# BRZ_BATT_MGR.net
KiCad netlist of a schematic drawn in Altium Designer
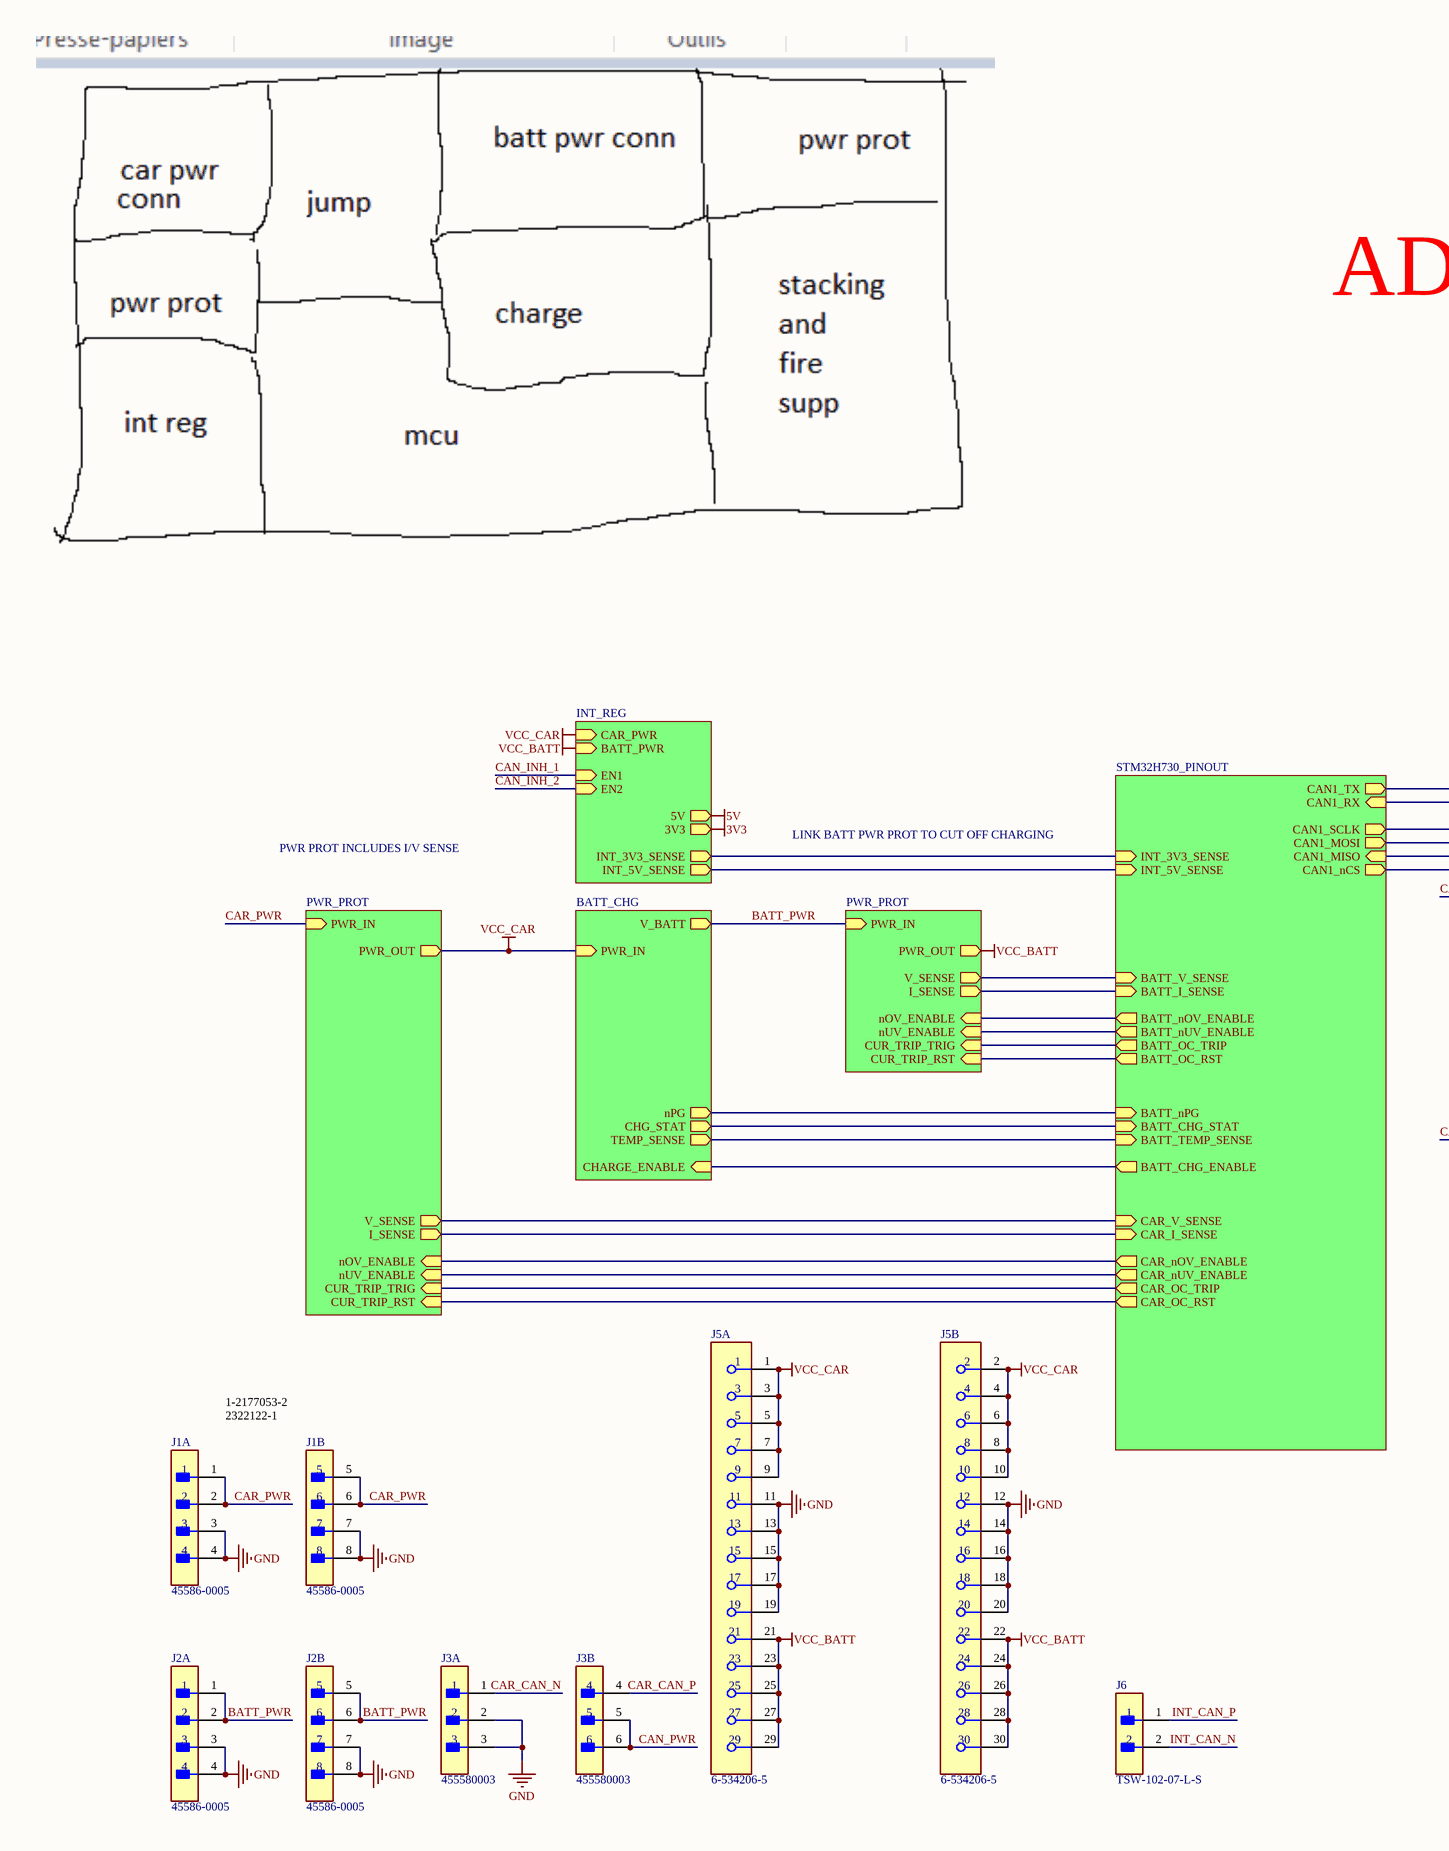
[diagram p0: BRZ_BATT_MGR.SchDoc, left]
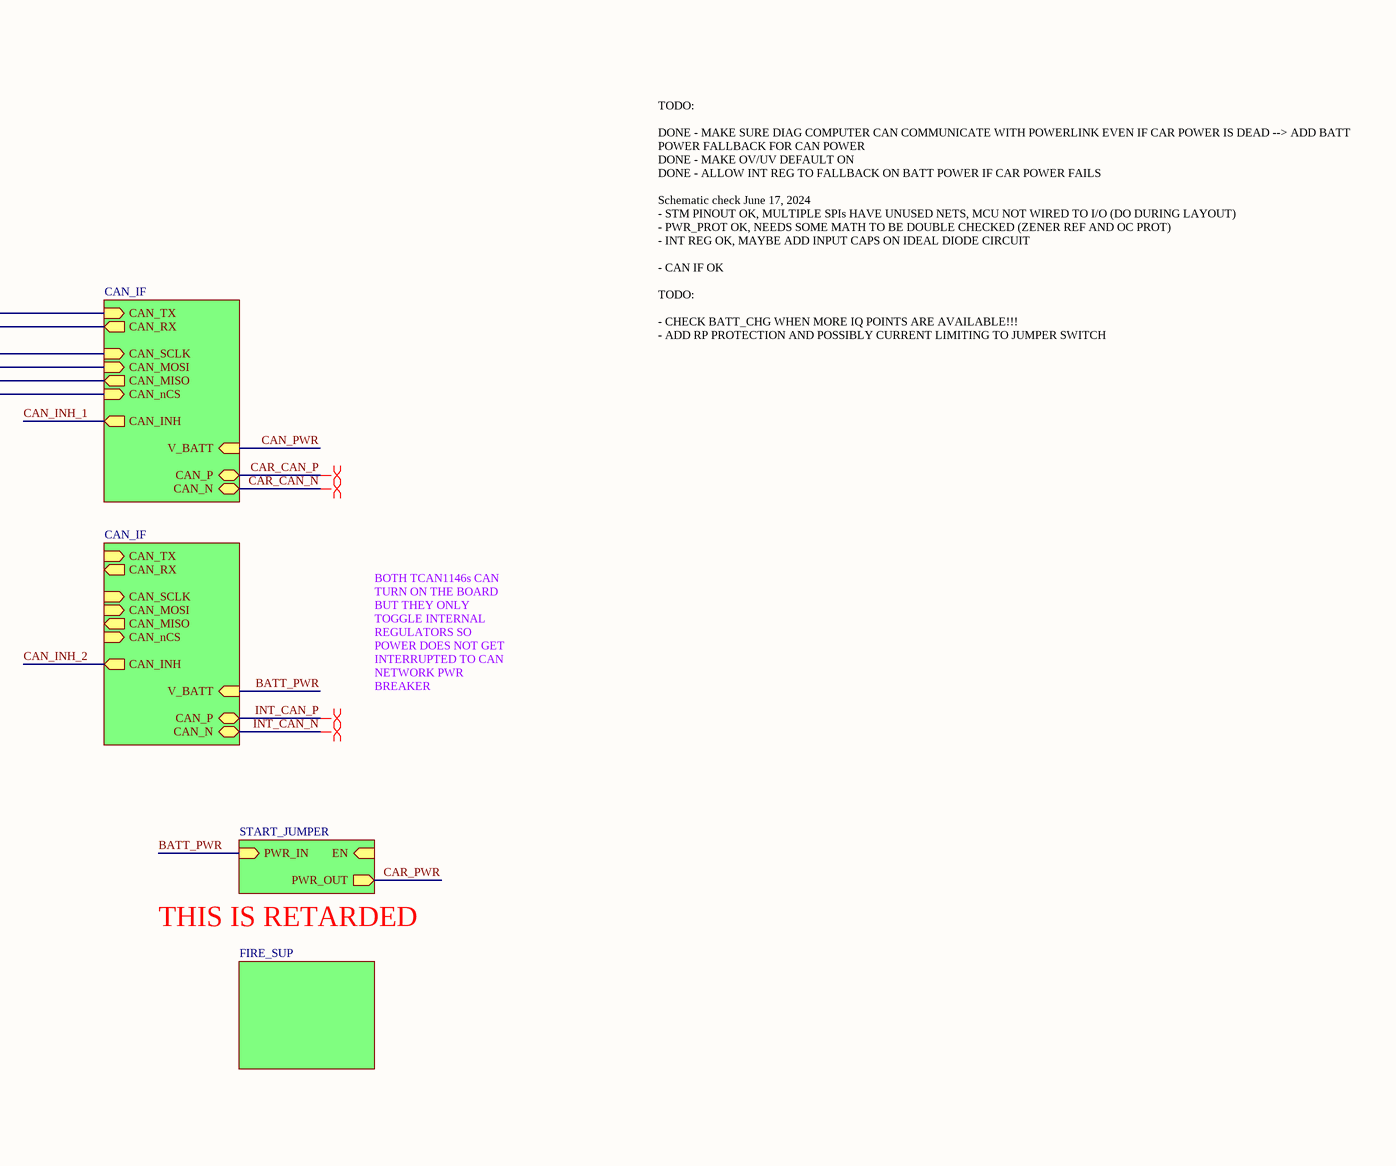
[diagram p1: BRZ_BATT_MGR.SchDoc, right]

(export (version "E")
  (design (tool "Eeschema 10.0.6"))
  (components
    (comp (ref "J1")
      (value "45586-0005")
      (footprint "FP-45586-0005-MFG")
      (description "CONN HEADER R/A 8POS 4.2MM")
      (libsource (lib "Altium Content Vault") (part "85438c39ca9ef07d43bb2e97c52bc44"))
    )
    (comp (ref "J2")
      (value "45586-0005")
      (footprint "FP-45586-0005-MFG")
      (description "CONN HEADER R/A 8POS 4.2MM")
      (libsource (lib "Altium Content Vault") (part "85438c39ca9ef07d43bb2e97c52bc44"))
    )
    (comp (ref "J3")
      (value "455580003")
      (footprint "FP-455580003-MFG")
      (description "CONN HEADER R/A 6POS 4.2MM")
      (fields
        (field (name "OCTOPART") "https://octopart.com/45558-0003-molex-7672845")
        (field (name "MANUFACTURER") "Molex")
      )
      (libsource (lib "Altium Content Vault") (part "bb9cbdb24149a20ba329b4e86909569"))
    )
    (comp (ref "J5")
      (value "6-534206-5")
      (footprint "FP-6-534206-5-MFG")
      (description "CONN RCPT 30POS 0.1 GOLD PCB")
      (fields
        (field (name "MANUFACTURER") "TE")
        (field (name "OCTOPART") "https://octopart.com/6-534206-5-te+connectivity-39516817")
      )
      (libsource (lib "Altium Content Vault") (part "58658856964e77fd1e9d81751433862"))
    )
    (comp (ref "J6")
      (value "TSW-102-07-L-S")
      (footprint "FP-TSW-102-07-L-S-MFG")
      (description "CONN HEADER VERT 2POS 2.54MM")
      (libsource (lib "Altium Content Vault") (part "3bc925449376181038e59eaffc5286c"))
    )
  )
  (nets
    (net (code "4") (name "/BATT_PWR") (class "Default")
      (node (ref "J2") (pin "1") (pinfunction "1_1") (pintype "passive"))
      (node (ref "J2") (pin "2") (pinfunction "2_2") (pintype "passive"))
      (node (ref "J2") (pin "5") (pinfunction "5_5") (pintype "passive"))
      (node (ref "J2") (pin "6") (pinfunction "6_6") (pintype "passive"))
    )
    (net (code "16") (name "/CAN_PWR") (class "Default")
      (node (ref "J3") (pin "5") (pinfunction "5_5") (pintype "passive"))
      (node (ref "J3") (pin "6") (pinfunction "6_6") (pintype "passive"))
    )
    (net (code "22") (name "/CAR_CAN_N") (class "Default")
      (node (ref "J3") (pin "1") (pinfunction "1_1") (pintype "passive"))
    )
    (net (code "23") (name "/CAR_CAN_P") (class "Default")
      (node (ref "J3") (pin "4") (pinfunction "4_4") (pintype "passive"))
    )
    (net (code "26") (name "/CAR_PWR") (class "Default")
      (node (ref "J1") (pin "1") (pinfunction "1_1") (pintype "passive"))
      (node (ref "J1") (pin "2") (pinfunction "2_2") (pintype "passive"))
      (node (ref "J1") (pin "5") (pinfunction "5_5") (pintype "passive"))
      (node (ref "J1") (pin "6") (pinfunction "6_6") (pintype "passive"))
    )
    (net (code "33") (name "/INT_CAN_N") (class "Default")
      (node (ref "J6") (pin "2") (pinfunction "2_2") (pintype "passive"))
    )
    (net (code "34") (name "/INT_CAN_P") (class "Default")
      (node (ref "J6") (pin "1") (pinfunction "1_1") (pintype "passive"))
    )
    (net (code "43") (name "GND") (class "Default")
      (node (ref "J1") (pin "3") (pinfunction "3_3") (pintype "passive"))
      (node (ref "J1") (pin "4") (pinfunction "4_4") (pintype "passive"))
      (node (ref "J1") (pin "7") (pinfunction "7_7") (pintype "passive"))
      (node (ref "J1") (pin "8") (pinfunction "8_8") (pintype "passive"))
      (node (ref "J2") (pin "3") (pinfunction "3_3") (pintype "passive"))
      (node (ref "J2") (pin "4") (pinfunction "4_4") (pintype "passive"))
      (node (ref "J2") (pin "7") (pinfunction "7_7") (pintype "passive"))
      (node (ref "J2") (pin "8") (pinfunction "8_8") (pintype "passive"))
      (node (ref "J3") (pin "2") (pinfunction "2_2") (pintype "passive"))
      (node (ref "J3") (pin "3") (pinfunction "3_3") (pintype "passive"))
      (node (ref "J5") (pin "11") (pinfunction "11_11") (pintype "passive"))
      (node (ref "J5") (pin "12") (pinfunction "12_12") (pintype "passive"))
      (node (ref "J5") (pin "13") (pinfunction "13_13") (pintype "passive"))
      (node (ref "J5") (pin "14") (pinfunction "14_14") (pintype "passive"))
      (node (ref "J5") (pin "15") (pinfunction "15_15") (pintype "passive"))
      (node (ref "J5") (pin "16") (pinfunction "16_16") (pintype "passive"))
      (node (ref "J5") (pin "17") (pinfunction "17_17") (pintype "passive"))
      (node (ref "J5") (pin "18") (pinfunction "18_18") (pintype "passive"))
      (node (ref "J5") (pin "19") (pinfunction "19_19") (pintype "passive"))
      (node (ref "J5") (pin "20") (pinfunction "20_20") (pintype "passive"))
    )
    (net (code "44") (name "VCC_BATT") (class "Default")
      (node (ref "J5") (pin "21") (pinfunction "21_21") (pintype "passive"))
      (node (ref "J5") (pin "22") (pinfunction "22_22") (pintype "passive"))
      (node (ref "J5") (pin "23") (pinfunction "23_23") (pintype "passive"))
      (node (ref "J5") (pin "24") (pinfunction "24_24") (pintype "passive"))
      (node (ref "J5") (pin "25") (pinfunction "25_25") (pintype "passive"))
      (node (ref "J5") (pin "26") (pinfunction "26_26") (pintype "passive"))
      (node (ref "J5") (pin "27") (pinfunction "27_27") (pintype "passive"))
      (node (ref "J5") (pin "28") (pinfunction "28_28") (pintype "passive"))
      (node (ref "J5") (pin "29") (pinfunction "29_29") (pintype "passive"))
      (node (ref "J5") (pin "30") (pinfunction "30_30") (pintype "passive"))
    )
    (net (code "45") (name "VCC_CAR") (class "Default")
      (node (ref "J5") (pin "1") (pinfunction "1_1") (pintype "passive"))
      (node (ref "J5") (pin "10") (pinfunction "10_10") (pintype "passive"))
      (node (ref "J5") (pin "2") (pinfunction "2_2") (pintype "passive"))
      (node (ref "J5") (pin "3") (pinfunction "3_3") (pintype "passive"))
      (node (ref "J5") (pin "4") (pinfunction "4_4") (pintype "passive"))
      (node (ref "J5") (pin "5") (pinfunction "5_5") (pintype "passive"))
      (node (ref "J5") (pin "6") (pinfunction "6_6") (pintype "passive"))
      (node (ref "J5") (pin "7") (pinfunction "7_7") (pintype "passive"))
      (node (ref "J5") (pin "8") (pinfunction "8_8") (pintype "passive"))
      (node (ref "J5") (pin "9") (pinfunction "9_9") (pintype "passive"))
    )
  )
)
